# SCH_USB-hub-for-onboard-_no-tutorial__20.net
KiCad netlist of a schematic drawn in EasyEDA
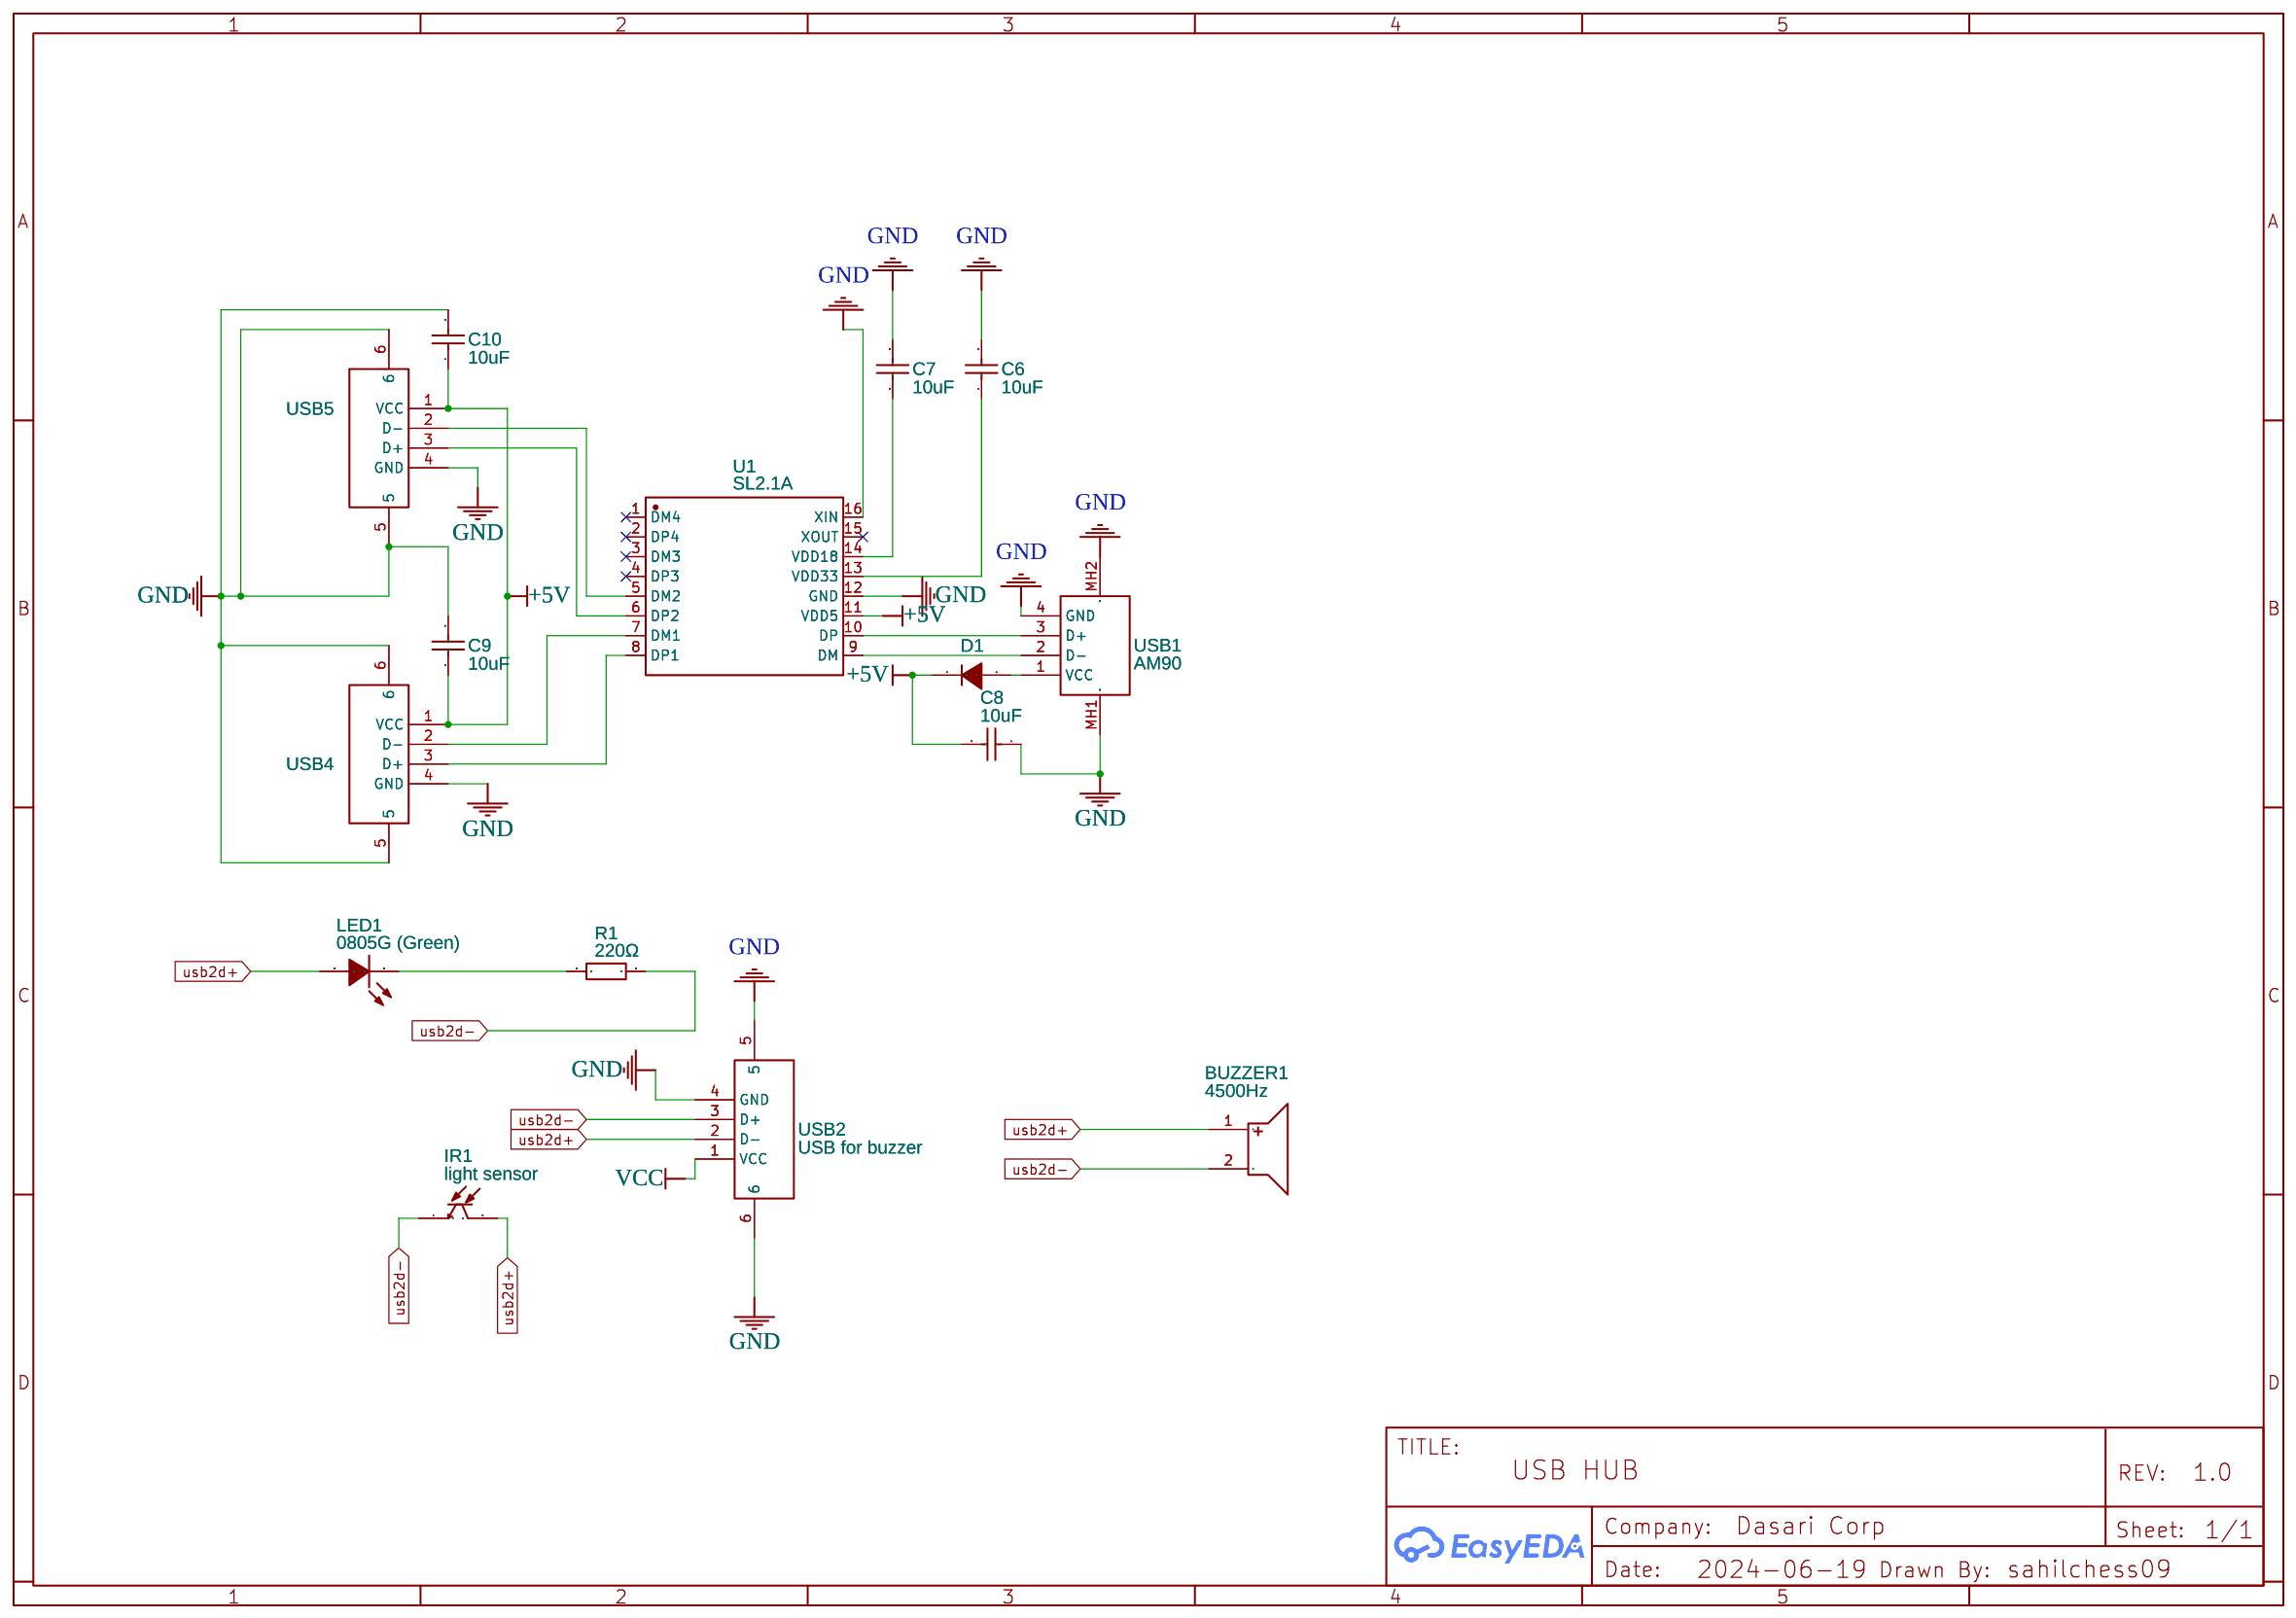
[diagram p0: schematic sheet]

(export (version "E")
  (design (tool "Eeschema 10.0.6"))
  (components
    (comp (ref "BUZZER1")
      (value "4500Hz")
      (fields (field (name "Manufacturer Part") "HND-1407B") (field (name "Manufacturer") "华能"))
      (libsource (lib "") (part "HND-1407B"))
    )
    (comp (ref "C6")
      (value "10uF")
      (fields
        (field (name "Manufacturer Part") "CL05A106MQ5NUNC")
        (field (name "Manufacturer") "SAMSUNG(三星)")
      )
      (libsource (lib "") (part "CL05A106MQ5NUNC"))
    )
    (comp (ref "C7")
      (value "10uF")
      (fields
        (field (name "Manufacturer Part") "CL05A106MQ5NUNC")
        (field (name "Manufacturer") "SAMSUNG(三星)")
      )
      (libsource (lib "") (part "CL05A106MQ5NUNC"))
    )
    (comp (ref "C8")
      (value "10uF")
      (fields
        (field (name "Manufacturer Part") "CL05A106MQ5NUNC")
        (field (name "Manufacturer") "SAMSUNG(三星)")
      )
      (libsource (lib "") (part "CL05A106MQ5NUNC_1"))
    )
    (comp (ref "C9")
      (value "10uF")
      (fields
        (field (name "Manufacturer Part") "CL05A106MQ5NUNC")
        (field (name "Manufacturer") "SAMSUNG(三星)")
      )
      (libsource (lib "") (part "CL05A106MQ5NUNC"))
    )
    (comp (ref "C10")
      (value "10uF")
      (fields
        (field (name "Manufacturer Part") "CL05A106MQ5NUNC")
        (field (name "Manufacturer") "SAMSUNG(三星)")
      )
      (libsource (lib "") (part "CL05A106MQ5NUNC"))
    )
    (comp (ref "D1")
      (value "‌")
      (fields (field (name "Manufacturer Part") "NSR0320MW2T1G") (field (name "Manufacturer") "onsemi(安森美)"))
      (libsource (lib "") (part "NSR0320MW2T1G"))
    )
    (comp (ref "IR1")
      (value "light sensor")
      (fields
        (field (name "Manufacturer Part") "PT928-6C(6-1)")
        (field (name "Manufacturer") "EVERLIGHT(亿光)")
      )
      (libsource (lib "") (part "PT928-6C(6-1)"))
    )
    (comp (ref "LED1")
      (value "0805G (Green)")
      (fields (field (name "Manufacturer Part") "KT-0805G") (field (name "Manufacturer") "KENTO"))
      (libsource (lib "") (part "0805G (Green)"))
    )
    (comp (ref "R1")
      (value "220Ω")
      (fields
        (field (name "Manufacturer Part") "0805W8F2200T5E")
        (field (name "Manufacturer") "UNI-ROYAL(厚声)")
      )
      (libsource (lib "") (part "0805W8F2200T5E"))
    )
    (comp (ref "U1")
      (value "SL2.1A")
      (fields (field (name "Manufacturer") "CoreChips(和芯润德)"))
      (libsource (lib "") (part "SL2.1A"))
    )
    (comp (ref "USB1")
      (value "AM90")
      (fields (field (name "Manufacturer") "SHOU HAN(首韩)"))
      (libsource (lib "") (part "AM90"))
    )
    (comp (ref "USB2")
      (value "USB for buzzer")
      (fields (field (name "Manufacturer Part") "903-131A1011D10100") (field (name "Manufacturer") "精拓金"))
      (libsource (lib "") (part "USB-AF-90-14.4X13.6-H7.0-DIP"))
    )
    (comp (ref "USB4")
      (value "USB-AF-90-14.4X13.6-H7.0-DIP")
      (fields (field (name "Manufacturer Part") "903-131A1011D10100") (field (name "Manufacturer") "精拓金"))
      (libsource (lib "") (part "USB-AF-90-14.4X13.6-H7.0-DIP_1"))
    )
    (comp (ref "USB5")
      (value "USB-AF-90-14.4X13.6-H7.0-DIP")
      (fields (field (name "Manufacturer Part") "903-131A1011D10100") (field (name "Manufacturer") "精拓金"))
      (libsource (lib "") (part "USB-AF-90-14.4X13.6-H7.0-DIP_1"))
    )
  )
  (nets
    (net (code "1") (name "+5V") (class "Default")
      (node (ref "C10") (pin "1") (pinfunction "1_1") (pintype "input"))
      (node (ref "C8") (pin "2") (pinfunction "2_2") (pintype "input"))
      (node (ref "C9") (pin "1") (pinfunction "1_1") (pintype "input"))
      (node (ref "D1") (pin "1") (pinfunction "C_1") (pintype "unspecified"))
      (node (ref "U1") (pin "11") (pinfunction "VDD5_11") (pintype "unspecified"))
      (node (ref "USB4") (pin "1") (pinfunction "VCC_1") (pintype "unspecified"))
      (node (ref "USB5") (pin "1") (pinfunction "VCC_1") (pintype "unspecified"))
    )
    (net (code "2") (name "GND") (class "Default")
      (node (ref "C10") (pin "2") (pinfunction "2_2") (pintype "input"))
      (node (ref "C6") (pin "2") (pinfunction "2_2") (pintype "input"))
      (node (ref "C7") (pin "2") (pinfunction "2_2") (pintype "input"))
      (node (ref "C8") (pin "1") (pinfunction "1_1") (pintype "input"))
      (node (ref "C9") (pin "2") (pinfunction "2_2") (pintype "input"))
      (node (ref "U1") (pin "12") (pinfunction "GND_12") (pintype "unspecified"))
      (node (ref "U1") (pin "16") (pinfunction "XIN_16") (pintype "unspecified"))
      (node (ref "USB1") (pin "4") (pinfunction "GND_4") (pintype "input"))
      (node (ref "USB1") (pin "MH1") (pinfunction "MH1_MH1") (pintype "unspecified"))
      (node (ref "USB1") (pin "MH2") (pinfunction "MH2_MH2") (pintype "unspecified"))
      (node (ref "USB2") (pin "4") (pinfunction "GND_4") (pintype "unspecified"))
      (node (ref "USB2") (pin "5") (pinfunction "5_5") (pintype "unspecified"))
      (node (ref "USB2") (pin "6") (pinfunction "6_6") (pintype "unspecified"))
      (node (ref "USB4") (pin "4") (pinfunction "GND_4") (pintype "unspecified"))
      (node (ref "USB4") (pin "5") (pinfunction "5_5") (pintype "unspecified"))
      (node (ref "USB4") (pin "6") (pinfunction "6_6") (pintype "unspecified"))
      (node (ref "USB5") (pin "4") (pinfunction "GND_4") (pintype "unspecified"))
      (node (ref "USB5") (pin "5") (pinfunction "5_5") (pintype "unspecified"))
      (node (ref "USB5") (pin "6") (pinfunction "6_6") (pintype "unspecified"))
    )
    (net (code "3") (name "Net-(D1-A)") (class "Default")
      (node (ref "D1") (pin "2") (pinfunction "A_2") (pintype "unspecified"))
      (node (ref "USB1") (pin "1") (pinfunction "VCC_1") (pintype "input"))
    )
    (net (code "4") (name "Net-(LED1-K)") (class "Default")
      (node (ref "LED1") (pin "2") (pinfunction "K_2") (pintype "unspecified"))
      (node (ref "R1") (pin "1") (pinfunction "1_1") (pintype "input"))
    )
    (net (code "5") (name "Net-(U1-DM)") (class "Default")
      (node (ref "U1") (pin "9") (pinfunction "DM_9") (pintype "unspecified"))
      (node (ref "USB1") (pin "2") (pinfunction "D-_2") (pintype "input"))
    )
    (net (code "6") (name "Net-(U1-DM1)") (class "Default")
      (node (ref "U1") (pin "7") (pinfunction "DM1_7") (pintype "unspecified"))
      (node (ref "USB4") (pin "2") (pinfunction "D-_2") (pintype "unspecified"))
    )
    (net (code "7") (name "Net-(U1-DM2)") (class "Default")
      (node (ref "U1") (pin "5") (pinfunction "DM2_5") (pintype "unspecified"))
      (node (ref "USB5") (pin "2") (pinfunction "D-_2") (pintype "unspecified"))
    )
    (net (code "8") (name "Net-(U1-DP)") (class "Default")
      (node (ref "U1") (pin "10") (pinfunction "DP_10") (pintype "unspecified"))
      (node (ref "USB1") (pin "3") (pinfunction "D+_3") (pintype "input"))
    )
    (net (code "9") (name "Net-(U1-DP1)") (class "Default")
      (node (ref "U1") (pin "8") (pinfunction "DP1_8") (pintype "unspecified"))
      (node (ref "USB4") (pin "3") (pinfunction "D+_3") (pintype "unspecified"))
    )
    (net (code "10") (name "Net-(U1-DP2)") (class "Default")
      (node (ref "U1") (pin "6") (pinfunction "DP2_6") (pintype "unspecified"))
      (node (ref "USB5") (pin "3") (pinfunction "D+_3") (pintype "unspecified"))
    )
    (net (code "11") (name "Net-(U1-VDD18)") (class "Default")
      (node (ref "C7") (pin "1") (pinfunction "1_1") (pintype "input"))
      (node (ref "U1") (pin "14") (pinfunction "VDD18_14") (pintype "unspecified"))
    )
    (net (code "12") (name "Net-(U1-VDD33)") (class "Default")
      (node (ref "C6") (pin "1") (pinfunction "1_1") (pintype "input"))
      (node (ref "U1") (pin "13") (pinfunction "VDD33_13") (pintype "unspecified"))
    )
    (net (code "13") (name "VCC") (class "Default")
      (node (ref "USB2") (pin "1") (pinfunction "VCC_1") (pintype "unspecified"))
    )
    (net (code "14") (name "unconnected-(U1-DM3-Pad3)") (class "Default")
      (node (ref "U1") (pin "3") (pinfunction "DM3_3") (pintype "unspecified+no_connect"))
    )
    (net (code "15") (name "unconnected-(U1-DM4-Pad1)") (class "Default")
      (node (ref "U1") (pin "1") (pinfunction "DM4_1") (pintype "unspecified+no_connect"))
    )
    (net (code "16") (name "unconnected-(U1-DP3-Pad4)") (class "Default")
      (node (ref "U1") (pin "4") (pinfunction "DP3_4") (pintype "unspecified+no_connect"))
    )
    (net (code "17") (name "unconnected-(U1-DP4-Pad2)") (class "Default")
      (node (ref "U1") (pin "2") (pinfunction "DP4_2") (pintype "unspecified+no_connect"))
    )
    (net (code "18") (name "unconnected-(U1-XOUT-Pad15)") (class "Default")
      (node (ref "U1") (pin "15") (pinfunction "XOUT_15") (pintype "unspecified+no_connect"))
    )
    (net (code "19") (name "usb2d+") (class "Default")
      (node (ref "BUZZER1") (pin "1") (pinfunction "1_1") (pintype "unspecified"))
      (node (ref "IR1") (pin "2") (pinfunction "C_2") (pintype "input"))
      (node (ref "LED1") (pin "1") (pinfunction "A_1") (pintype "unspecified"))
      (node (ref "USB2") (pin "2") (pinfunction "D-_2") (pintype "unspecified"))
    )
    (net (code "20") (name "usb2d-") (class "Default")
      (node (ref "BUZZER1") (pin "2") (pinfunction "2_2") (pintype "unspecified"))
      (node (ref "IR1") (pin "1") (pinfunction "E_1") (pintype "input"))
      (node (ref "R1") (pin "2") (pinfunction "2_2") (pintype "input"))
      (node (ref "USB2") (pin "3") (pinfunction "D+_3") (pintype "unspecified"))
    )
  )
)
